# HbHandBoardMk2_V4.net
KiCad netlist of a schematic drawn in EAGLE
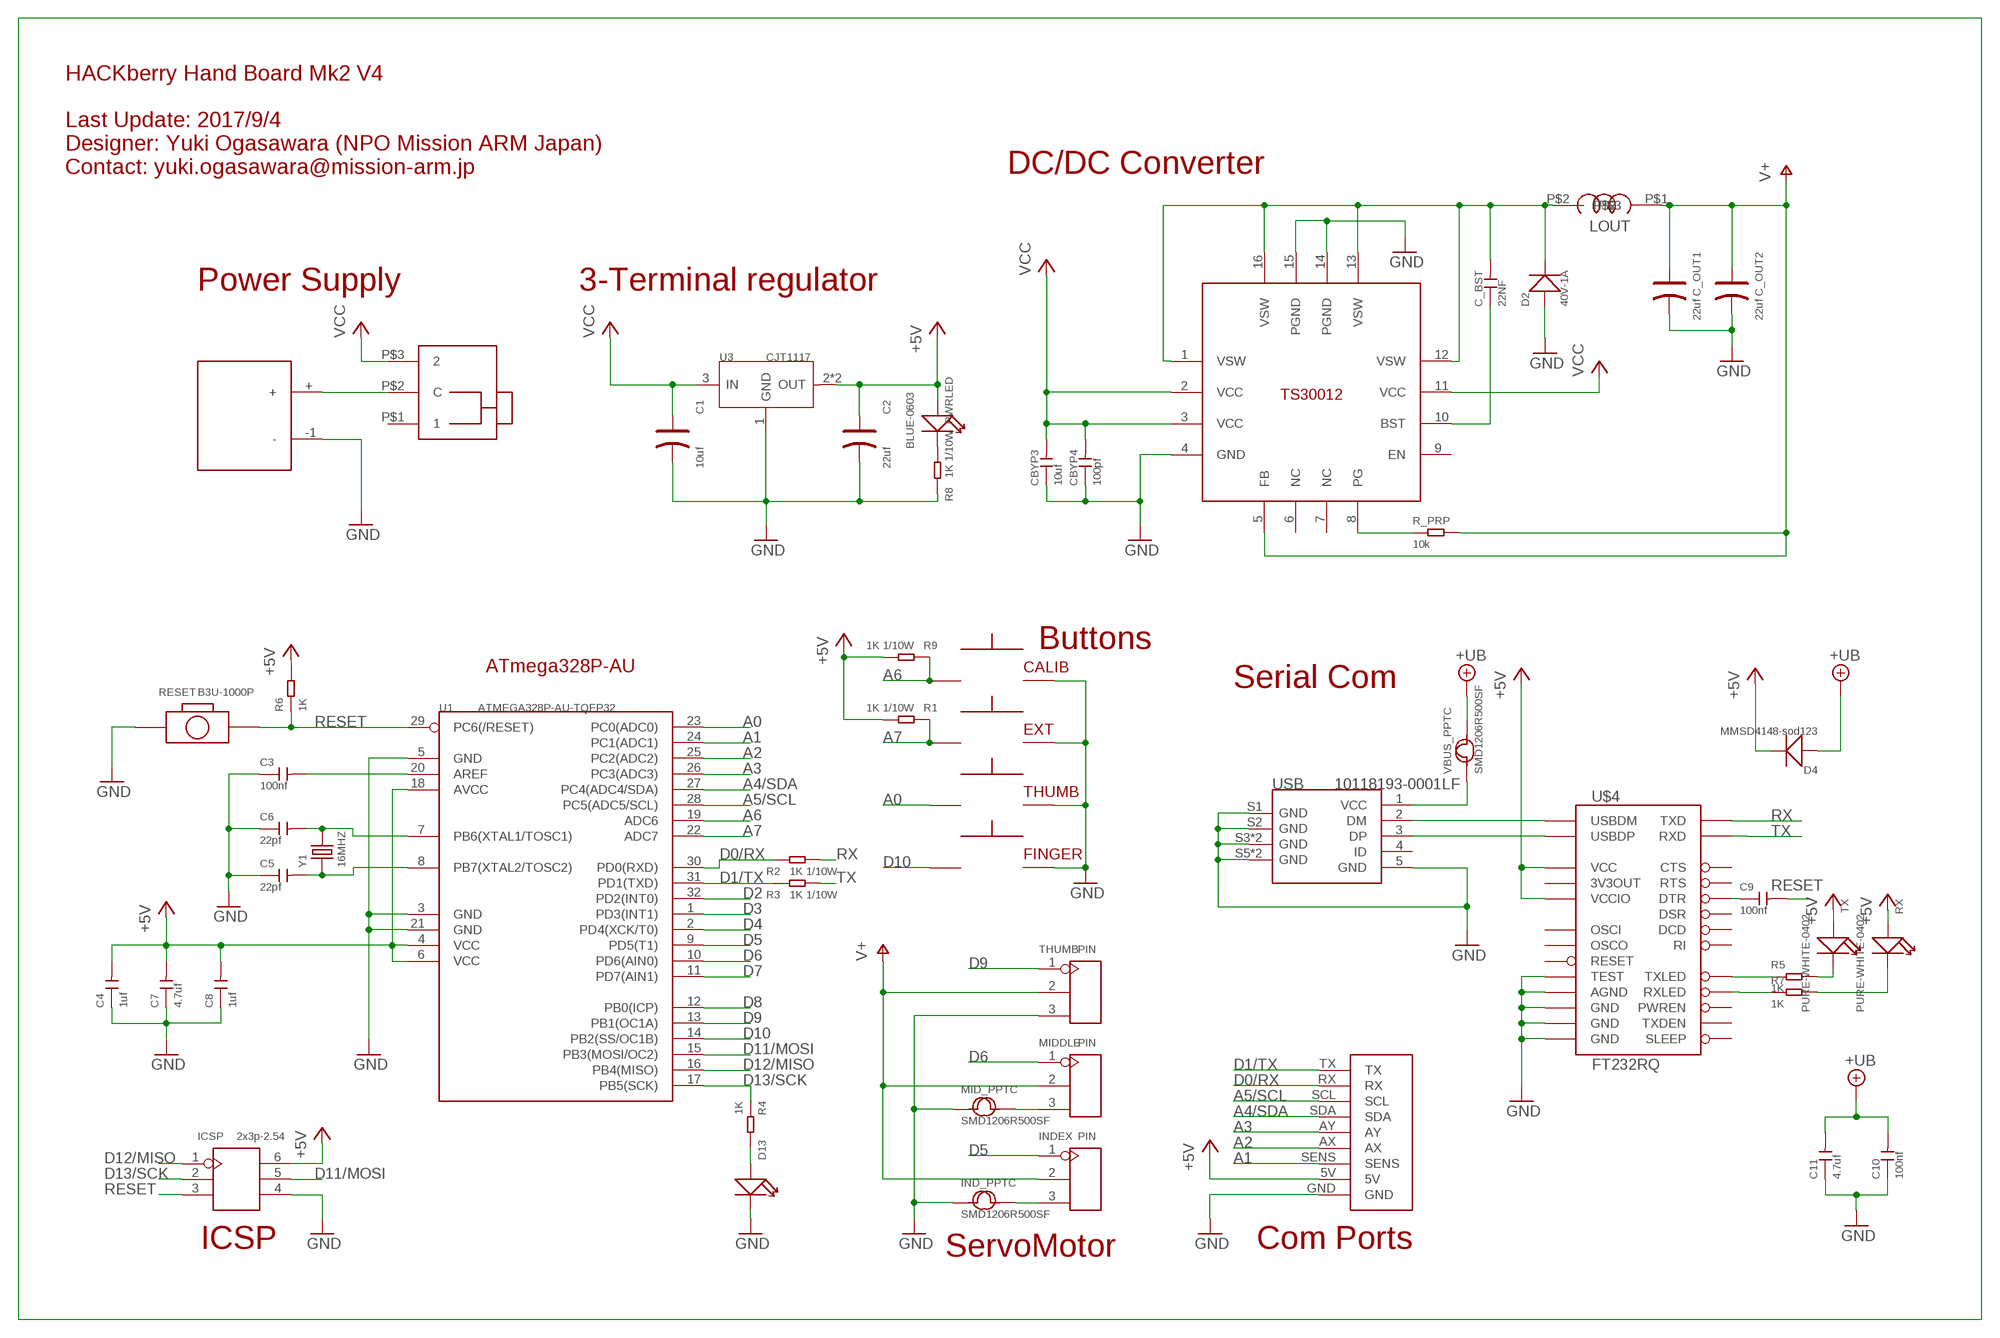
[diagram p0: schematic, sheet 1]

(export (version "E")
  (design (tool "Eeschema 10.0.6"))
  (components
    (comp (ref "C1")
      (value "10uf")
      (footprint "eagle-import:AVX-A")
      (fields (field (name "MPN") "TAJA106K010RNJ"))
      (libsource (lib "eagle-import") (part "TANTALUM-SMD-10UF-10V-10%(AVX-A)"))
    )
    (comp (ref "C2")
      (value "22uf")
      (footprint "eagle-import:AVX-A")
      (fields (field (name "MPN") "TAJA226*010#NJ"))
      (libsource (lib "eagle-import") (part "TANTALUM-SMD-22UF-10V(AVX-A)"))
    )
    (comp (ref "C3")
      (value "100nf")
      (footprint "eagle-import:C0402")
      (fields (field (name "MPN") "CC0402KRX7R8BB104"))
      (libsource (lib "eagle-import") (part "CERAMIC-100NF-25V-10%-X7R(0402)"))
    )
    (comp (ref "C4")
      (value "1uf")
      (footprint "eagle-import:C0402")
      (fields (field (name "MPN") "CC0402KRX5R6BB105"))
      (libsource (lib "eagle-import") (part "CERAMIC-1UF-10V-10%-X5R(0402)"))
    )
    (comp (ref "C5")
      (value "22pf")
      (footprint "eagle-import:C0402")
      (fields (field (name "MPN") "CC0402JRNPO9BN220"))
      (libsource (lib "eagle-import") (part "CERAMIC-22PF-50V-5%-NPO(0402)"))
    )
    (comp (ref "C6")
      (value "22pf")
      (footprint "eagle-import:C0402")
      (fields (field (name "MPN") "CC0402JRNPO9BN220"))
      (libsource (lib "eagle-import") (part "CERAMIC-22PF-50V-5%-NPO(0402)"))
    )
    (comp (ref "C7")
      (value "4.7uf")
      (footprint "eagle-import:C0603")
      (fields (field (name "MPN") "CC0603KRX5R6BB475"))
      (libsource (lib "eagle-import") (part "CERAMIC-4.7UF-10V-10%-X5R(0603)"))
    )
    (comp (ref "C8")
      (value "1uf")
      (footprint "eagle-import:C0402")
      (fields (field (name "MPN") "CC0402KRX5R6BB105"))
      (libsource (lib "eagle-import") (part "CERAMIC-1UF-10V-10%-X5R(0402)"))
    )
    (comp (ref "C9")
      (value "100nf")
      (footprint "eagle-import:C0402")
      (fields (field (name "MPN") "CC0402KRX7R8BB104"))
      (libsource (lib "eagle-import") (part "CERAMIC-100NF-25V-10%-X7R(0402)"))
    )
    (comp (ref "C10")
      (value "100nf")
      (footprint "eagle-import:C0402")
      (fields (field (name "MPN") "CC0402KRX7R8BB104"))
      (libsource (lib "eagle-import") (part "CERAMIC-100NF-25V-10%-X7R(0402)"))
    )
    (comp (ref "C11")
      (value "4.7uf")
      (footprint "eagle-import:C0603")
      (fields (field (name "MPN") "CC0603KRX5R6BB475"))
      (libsource (lib "eagle-import") (part "CERAMIC-4.7UF-10V-10%-X5R(0603)"))
    )
    (comp (ref "CALIB")
      (value "SKRGAQD010")
      (footprint "eagle-import:SKRGAQD010")
      (libsource (lib "eagle-import") (part "SKRGAQD010"))
    )
    (comp (ref "CBYP3")
      (value "10uf")
      (footprint "eagle-import:C0805")
      (fields (field (name "MPN") "CC0805KKX5R8BB106"))
      (libsource (lib "eagle-import") (part "CERAMIC-10UF-25V-10%-X5R(0805)"))
    )
    (comp (ref "CBYP4")
      (value "100pf")
      (footprint "eagle-import:C0402")
      (fields (field (name "MPN") "CC0402JRNPO9BN101"))
      (libsource (lib "eagle-import") (part "CERAMIC-100PF-50V-5%-NPO(0402)"))
    )
    (comp (ref "C_BST")
      (value "22NF")
      (footprint "eagle-import:C0402")
      (fields (field (name "MPN") "CC0402KRX7R9BB223"))
      (libsource (lib "eagle-import") (part "CERAMIC-22NF-50V-10%-X7R(0402)"))
    )
    (comp (ref "C_OUT1")
      (value "22uf")
      (footprint "eagle-import:AVX-B")
      (fields (field (name "MPN") "TAJB226K010RNJ"))
      (libsource (lib "eagle-import") (part "TANTALUM-SMD-22UF-10V-10%(AVX-B)"))
    )
    (comp (ref "C_OUT2")
      (value "22uf")
      (footprint "eagle-import:AVX-B")
      (fields (field (name "MPN") "TAJB226K010RNJ"))
      (libsource (lib "eagle-import") (part "TANTALUM-SMD-22UF-10V-10%(AVX-B)"))
    )
    (comp (ref "D2")
      (value "40V-1A")
      (footprint "eagle-import:DO-214AC")
      (fields (field (name "MPN") "1N5819"))
      (libsource (lib "eagle-import") (part "SMD-DIODE-SCHOTTKY-40V-1A(DO-214AC)"))
    )
    (comp (ref "D4")
      (value "MMSD4148-sod123")
      (footprint "eagle-import:SOD-123")
      (fields (field (name "MPN") "MMSD4148"))
      (libsource (lib "eagle-import") (part "SMD-DIODE-100V-200MA(SOD-123)"))
    )
    (comp (ref "D13")
      (value "SMD-LED-CLEAR-GREEN(0805)")
      (footprint "eagle-import:LED-0805")
      (fields (field (name "MPN") "17-215SYGC/S530-E2/TR8"))
      (libsource (lib "eagle-import") (part "SMD-LED-CLEAR-GREEN(0805)"))
    )
    (comp (ref "EXT")
      (value "SKRGAQD010")
      (footprint "eagle-import:SKRGAQD010")
      (libsource (lib "eagle-import") (part "SKRGAQD010"))
    )
    (comp (ref "FINGER")
      (value "SKRGAQD010")
      (footprint "eagle-import:SKRGAQD010")
      (libsource (lib "eagle-import") (part "SKRGAQD010"))
    )
    (comp (ref "ICSP")
      (value "2x3p-2.54")
      (footprint "eagle-import:H2X3-2.54")
      (fields (field (name "MPN") "P125-12A1BS116A1"))
      (libsource (lib "eagle-import") (part "DIP-BLACK-MALE-HEADER(2X3P-2.54）-2.54"))
    )
    (comp (ref "INDEX")
      (value "PIN")
      (footprint "eagle-import:H3-2.54")
      (fields (field (name "MPN") "F185-1103A0BSYA1"))
      (libsource (lib "eagle-import") (part "DIP-BLACK-FEMALE-HEADER-VERT(3P-2.54)"))
    )
    (comp (ref "IND_PPTC")
      (value "SMD1206R500SF")
      (footprint "eagle-import:F1206")
      (libsource (lib "eagle-import") (part "SMD-PPTC-500MA(1206)"))
    )
    (comp (ref "LOUT")
      (value "SPM3015T-4R7M-LR")
      (footprint "eagle-import:SPM3015T-4R7M-LR")
      (libsource (lib "eagle-import") (part "SPM3015T-4R7M-LR"))
    )
    (comp (ref "MIDDLE")
      (value "PIN")
      (footprint "eagle-import:H3-2.54")
      (fields (field (name "MPN") "F185-1103A0BSYA1"))
      (libsource (lib "eagle-import") (part "DIP-BLACK-FEMALE-HEADER-VERT(3P-2.54)"))
    )
    (comp (ref "MID_PPTC")
      (value "SMD1206R500SF")
      (footprint "eagle-import:F1206")
      (libsource (lib "eagle-import") (part "SMD-PPTC-500MA(1206)"))
    )
    (comp (ref "PWRLED")
      (value "BLUE-0603")
      (footprint "eagle-import:LED-0603")
      (fields (field (name "MPN") "19-217-BHC-ZL1M2RY-3T"))
      (libsource (lib "eagle-import") (part "SMD-LED-CLEAR-BLUE(0603)"))
    )
    (comp (ref "PWR_SW")
      (value "SS12SDP2")
      (footprint "eagle-import:SS12SDP2")
      (libsource (lib "eagle-import") (part "SS12SDP2"))
    )
    (comp (ref "R1")
      (value "1K 1/10W")
      (footprint "eagle-import:R0603")
      (fields (field (name "MPN") "RC0603JR-071KL"))
      (libsource (lib "eagle-import") (part "SMD-RES-1K-5%-1/10W(0603)"))
    )
    (comp (ref "R2")
      (value "1K 1/10W")
      (footprint "eagle-import:R0603")
      (fields (field (name "MPN") "RC0603JR-071KL"))
      (libsource (lib "eagle-import") (part "SMD-RES-1K-5%-1/10W(0603)"))
    )
    (comp (ref "R3")
      (value "1K 1/10W")
      (footprint "eagle-import:R0603")
      (fields (field (name "MPN") "RC0603JR-071KL"))
      (libsource (lib "eagle-import") (part "SMD-RES-1K-5%-1/10W(0603)"))
    )
    (comp (ref "R4")
      (value "1K")
      (footprint "eagle-import:R0805")
      (fields (field (name "MPN") "RC0805JR-071KL"))
      (libsource (lib "eagle-import") (part "SMD-RES-1K-5%-1/8W(0805)"))
    )
    (comp (ref "R5")
      (value "1K")
      (footprint "eagle-import:R0402")
      (fields (field (name "MPN") "RC0402JR-071KL"))
      (libsource (lib "eagle-import") (part "SMD-RES-1K-5%-1/16W(0402)"))
    )
    (comp (ref "R6")
      (value "1K")
      (footprint "eagle-import:R0402")
      (fields (field (name "MPN") "RC0402JR-071KL"))
      (libsource (lib "eagle-import") (part "SMD-RES-1K-5%-1/16W(0402)"))
    )
    (comp (ref "R7")
      (value "1K")
      (footprint "eagle-import:R0402")
      (fields (field (name "MPN") "RC0402JR-071KL"))
      (libsource (lib "eagle-import") (part "SMD-RES-1K-5%-1/16W(0402)"))
    )
    (comp (ref "R8")
      (value "1K 1/10W")
      (footprint "eagle-import:R0603")
      (fields (field (name "MPN") "RC0603JR-071KL"))
      (libsource (lib "eagle-import") (part "SMD-RES-1K-5%-1/10W(0603)"))
    )
    (comp (ref "R9")
      (value "1K 1/10W")
      (footprint "eagle-import:R0603")
      (fields (field (name "MPN") "RC0603JR-071KL"))
      (libsource (lib "eagle-import") (part "SMD-RES-1K-5%-1/10W(0603)"))
    )
    (comp (ref "RESET")
      (value "B3U-1000P")
      (footprint "eagle-import:SW2-SMD-3.0X2.5X1.2+0.4MM")
      (libsource (lib "eagle-import") (part "SMD-BUTTON-WITHOUT-BOSS-(2P-3X2.5MM)"))
    )
    (comp (ref "RX")
      (value "PURE-WHITE-0402")
      (footprint "eagle-import:LED-0402")
      (fields (field (name "MPN") "16-219A/T2D-AR2T1QY/3T"))
      (libsource (lib "eagle-import") (part "SMD-LED-YELLOW-DIFFUSED-PURE-WHITE(0402)"))
    )
    (comp (ref "R_PRP")
      (value "10k")
      (footprint "eagle-import:R0402")
      (libsource (lib "eagle-import") (part "RES-0402"))
    )
    (comp (ref "THUMB")
      (value "PIN")
      (footprint "eagle-import:H3-2.54")
      (fields (field (name "MPN") "F185-1103A0BSYA1"))
      (libsource (lib "eagle-import") (part "DIP-BLACK-FEMALE-HEADER-VERT(3P-2.54)"))
    )
    (comp (ref "THUMB_BUTTON")
      (value "SKRGAQD010")
      (footprint "eagle-import:SKRGAQD010")
      (libsource (lib "eagle-import") (part "SKRGAQD010"))
    )
    (comp (ref "TX")
      (value "PURE-WHITE-0402")
      (footprint "eagle-import:LED-0402")
      (fields (field (name "MPN") "16-219A/T2D-AR2T1QY/3T"))
      (libsource (lib "eagle-import") (part "SMD-LED-YELLOW-DIFFUSED-PURE-WHITE(0402)"))
    )
    (comp (ref "U$1")
      (value "9PADS")
      (footprint "eagle-import:9PADS")
      (libsource (lib "eagle-import") (part "9PADS"))
    )
    (comp (ref "U$3")
      (value "DCJACK")
      (footprint "eagle-import:DCJ3P-14.2X11.0X9.0MM")
      (libsource (lib "eagle-import") (part "DCJACK"))
    )
    (comp (ref "U$4")
      (value "FT232RQ")
      (footprint "eagle-import:QFN-32")
      (fields (field (name "MF") "FTDI"))
      (libsource (lib "eagle-import") (part "FT232RQ"))
    )
    (comp (ref "U$6")
      (value "TS30012")
      (footprint "eagle-import:VQFN16")
      (libsource (lib "eagle-import") (part "TS30012"))
    )
    (comp (ref "U1")
      (value "ATMEGA328P-AU-TQFP32")
      (footprint "eagle-import:TQFP32-0.8-7X7MM")
      (fields (field (name "MPN") "ATMEGA328P-AU"))
      (libsource (lib "eagle-import") (part "MCU-ATMEGA328P-AU(TQFP32)"))
    )
    (comp (ref "U3")
      (value "CJT1117")
      (footprint "eagle-import:SOT-223")
      (fields (field (name "MPN") "CJT1117-5.0"))
      (libsource (lib "eagle-import") (part "PMIC-CJT1117-5.0(SOT223)"))
    )
    (comp (ref "USB")
      (value "10118193-0001LF")
      (footprint "eagle-import:MICRO-USB5+6P-SMD-0.65-B")
      (libsource (lib "eagle-import") (part "MICRO-USB-SMD-B-(10118193-0001LF)"))
    )
    (comp (ref "VBUS_PPTC")
      (value "SMD1206R500SF")
      (footprint "eagle-import:F1206")
      (libsource (lib "eagle-import") (part "SMD-PPTC-500MA(1206)"))
    )
    (comp (ref "Y1")
      (value "16MHZ")
      (footprint "eagle-import:X2-SMD-5.0X3.2X1.3MM")
      (fields (field (name "MPN") "X053201602002"))
      (libsource (lib "eagle-import") (part "SMD-CRYSTAL-16MHZ-8PF-20PPM-40R(2P-5.0X3.2MM)"))
    )
  )
  (nets
    (net (code "1") (name "+5V") (class "Default")
      (node (ref "C2") (pin "+") (pinfunction "+_+") (pintype "passive"))
      (node (ref "C4") (pin "2") (pinfunction "2_2") (pintype "passive"))
      (node (ref "C7") (pin "2") (pinfunction "2_2") (pintype "passive"))
      (node (ref "C8") (pin "2") (pinfunction "2_2") (pintype "passive"))
      (node (ref "D4") (pin "-") (pinfunction "-_-") (pintype "passive"))
      (node (ref "ICSP") (pin "6") (pinfunction "6_6") (pintype "bidirectional"))
      (node (ref "PWRLED") (pin "+") (pinfunction "+_+") (pintype "passive"))
      (node (ref "R1") (pin "2") (pinfunction "2_2") (pintype "passive"))
      (node (ref "R6") (pin "2") (pinfunction "2_2") (pintype "passive"))
      (node (ref "R9") (pin "2") (pinfunction "2_2") (pintype "passive"))
      (node (ref "RX") (pin "+") (pinfunction "+_+") (pintype "passive"))
      (node (ref "TX") (pin "+") (pinfunction "+_+") (pintype "passive"))
      (node (ref "U$1") (pin "5V") (pinfunction "5V_5V") (pintype "bidirectional"))
      (node (ref "U$4") (pin "1") (pinfunction "VCCIO_1") (pintype "power_in"))
      (node (ref "U$4") (pin "19") (pinfunction "VCC_19") (pintype "power_in"))
      (node (ref "U1") (pin "18") (pinfunction "AVCC_18") (pintype "bidirectional"))
      (node (ref "U1") (pin "4") (pinfunction "VCC_4") (pintype "bidirectional"))
      (node (ref "U1") (pin "6") (pinfunction "VCC_6") (pintype "bidirectional"))
      (node (ref "U3") (pin "2") (pinfunction "OUT_2") (pintype "bidirectional"))
      (node (ref "U3") (pin "TER") (pinfunction "OUT_TER") (pintype "bidirectional"))
    )
    (net (code "2") (name "+UB") (class "Default")
      (node (ref "C10") (pin "2") (pinfunction "2_2") (pintype "passive"))
      (node (ref "C11") (pin "2") (pinfunction "2_2") (pintype "passive"))
      (node (ref "D4") (pin "+") (pinfunction "+_+") (pintype "passive"))
      (node (ref "VBUS_PPTC") (pin "2") (pinfunction "2_2") (pintype "bidirectional"))
    )
    (net (code "3") (name "/A0") (class "Default")
      (node (ref "THUMB_BUTTON") (pin "P$1") (pinfunction "1_P$1") (pintype "bidirectional"))
      (node (ref "U1") (pin "23") (pinfunction "PC0(ADC0)_23") (pintype "bidirectional"))
    )
    (net (code "4") (name "/A1") (class "Default")
      (node (ref "U$1") (pin "SENS") (pinfunction "SENS_SENS") (pintype "bidirectional"))
      (node (ref "U1") (pin "24") (pinfunction "PC1(ADC1)_24") (pintype "bidirectional"))
    )
    (net (code "5") (name "/A2") (class "Default")
      (node (ref "U$1") (pin "AX") (pinfunction "AX_AX") (pintype "bidirectional"))
      (node (ref "U1") (pin "25") (pinfunction "PC2(ADC2)_25") (pintype "bidirectional"))
    )
    (net (code "6") (name "/A3") (class "Default")
      (node (ref "U$1") (pin "AY") (pinfunction "AY_AY") (pintype "bidirectional"))
      (node (ref "U1") (pin "26") (pinfunction "PC3(ADC3)_26") (pintype "bidirectional"))
    )
    (net (code "7") (name "/A4{slash}SDA") (class "Default")
      (node (ref "U$1") (pin "SDA") (pinfunction "SDA_SDA") (pintype "bidirectional"))
      (node (ref "U1") (pin "27") (pinfunction "PC4(ADC4/SDA)_27") (pintype "bidirectional"))
    )
    (net (code "8") (name "/A5{slash}SCL") (class "Default")
      (node (ref "U$1") (pin "SCL") (pinfunction "SCL_SCL") (pintype "bidirectional"))
      (node (ref "U1") (pin "28") (pinfunction "PC5(ADC5/SCL)_28") (pintype "bidirectional"))
    )
    (net (code "9") (name "/A6") (class "Default")
      (node (ref "CALIB") (pin "P$1") (pinfunction "1_P$1") (pintype "bidirectional"))
      (node (ref "R9") (pin "1") (pinfunction "1_1") (pintype "passive"))
      (node (ref "U1") (pin "19") (pinfunction "ADC6_19") (pintype "bidirectional"))
    )
    (net (code "10") (name "/A7") (class "Default")
      (node (ref "EXT") (pin "P$1") (pinfunction "1_P$1") (pintype "bidirectional"))
      (node (ref "R1") (pin "1") (pinfunction "1_1") (pintype "passive"))
      (node (ref "U1") (pin "22") (pinfunction "ADC7_22") (pintype "bidirectional"))
    )
    (net (code "11") (name "/D0{slash}RX") (class "Default")
      (node (ref "R2") (pin "1") (pinfunction "1_1") (pintype "passive"))
      (node (ref "U$1") (pin "RX") (pinfunction "RX_RX") (pintype "bidirectional"))
      (node (ref "U1") (pin "30") (pinfunction "PD0(RXD)_30") (pintype "bidirectional"))
    )
    (net (code "12") (name "/D1{slash}TX") (class "Default")
      (node (ref "R3") (pin "1") (pinfunction "1_1") (pintype "passive"))
      (node (ref "U$1") (pin "TX") (pinfunction "TX_TX") (pintype "bidirectional"))
      (node (ref "U1") (pin "31") (pinfunction "PD1(TXD)_31") (pintype "bidirectional"))
    )
    (net (code "13") (name "/D2") (class "Default")
      (node (ref "U1") (pin "32") (pinfunction "PD2(INT0)_32") (pintype "bidirectional"))
    )
    (net (code "14") (name "/D3") (class "Default")
      (node (ref "U1") (pin "1") (pinfunction "PD3(INT1)_1") (pintype "bidirectional"))
    )
    (net (code "15") (name "/D4") (class "Default")
      (node (ref "U1") (pin "2") (pinfunction "PD4(XCK/T0)_2") (pintype "bidirectional"))
    )
    (net (code "16") (name "/D5") (class "Default")
      (node (ref "INDEX") (pin "1") (pinfunction "P$1_1") (pintype "bidirectional"))
      (node (ref "U1") (pin "9") (pinfunction "PD5(T1)_9") (pintype "bidirectional"))
    )
    (net (code "17") (name "/D6") (class "Default")
      (node (ref "MIDDLE") (pin "1") (pinfunction "P$1_1") (pintype "bidirectional"))
      (node (ref "U1") (pin "10") (pinfunction "PD6(AIN0)_10") (pintype "bidirectional"))
    )
    (net (code "18") (name "/D7") (class "Default")
      (node (ref "U1") (pin "11") (pinfunction "PD7(AIN1)_11") (pintype "bidirectional"))
    )
    (net (code "19") (name "/D8") (class "Default")
      (node (ref "U1") (pin "12") (pinfunction "PB0(ICP)_12") (pintype "bidirectional"))
    )
    (net (code "20") (name "/D9") (class "Default")
      (node (ref "THUMB") (pin "1") (pinfunction "P$1_1") (pintype "bidirectional"))
      (node (ref "U1") (pin "13") (pinfunction "PB1(OC1A)_13") (pintype "bidirectional"))
    )
    (net (code "21") (name "/D10") (class "Default")
      (node (ref "FINGER") (pin "P$1") (pinfunction "1_P$1") (pintype "bidirectional"))
      (node (ref "U1") (pin "14") (pinfunction "PB2(SS/OC1B)_14") (pintype "bidirectional"))
    )
    (net (code "22") (name "/D11{slash}MOSI") (class "Default")
      (node (ref "ICSP") (pin "5") (pinfunction "5_5") (pintype "bidirectional"))
      (node (ref "U1") (pin "15") (pinfunction "PB3(MOSI/OC2)_15") (pintype "bidirectional"))
    )
    (net (code "23") (name "/D12{slash}MISO") (class "Default")
      (node (ref "ICSP") (pin "1") (pinfunction "1_1") (pintype "bidirectional"))
      (node (ref "U1") (pin "16") (pinfunction "PB4(MISO)_16") (pintype "bidirectional"))
    )
    (net (code "24") (name "/D13{slash}SCK") (class "Default")
      (node (ref "ICSP") (pin "2") (pinfunction "2_2") (pintype "bidirectional"))
      (node (ref "R4") (pin "1") (pinfunction "1_1") (pintype "passive"))
      (node (ref "U1") (pin "17") (pinfunction "PB5(SCK)_17") (pintype "bidirectional"))
    )
    (net (code "25") (name "/RESET") (class "Default")
      (node (ref "C9") (pin "2") (pinfunction "2_2") (pintype "passive"))
      (node (ref "ICSP") (pin "3") (pinfunction "3_3") (pintype "bidirectional"))
      (node (ref "R6") (pin "1") (pinfunction "1_1") (pintype "passive"))
      (node (ref "RESET") (pin "2") (pinfunction "2_2") (pintype "bidirectional"))
      (node (ref "U1") (pin "29") (pinfunction "PC6(/RESET)_29") (pintype "bidirectional"))
    )
    (net (code "26") (name "/RX") (class "Default")
      (node (ref "R2") (pin "2") (pinfunction "2_2") (pintype "passive"))
      (node (ref "U$4") (pin "30") (pinfunction "TXD_30") (pintype "output"))
    )
    (net (code "27") (name "/TX") (class "Default")
      (node (ref "R3") (pin "2") (pinfunction "2_2") (pintype "passive"))
      (node (ref "U$4") (pin "2") (pinfunction "RXD_2") (pintype "input"))
    )
    (net (code "28") (name "GND") (class "Default")
      (node (ref "C1") (pin "-") (pinfunction "-_-") (pintype "passive"))
      (node (ref "C10") (pin "1") (pinfunction "1_1") (pintype "passive"))
      (node (ref "C11") (pin "1") (pinfunction "1_1") (pintype "passive"))
      (node (ref "C2") (pin "-") (pinfunction "-_-") (pintype "passive"))
      (node (ref "C3") (pin "1") (pinfunction "1_1") (pintype "passive"))
      (node (ref "C4") (pin "1") (pinfunction "1_1") (pintype "passive"))
      (node (ref "C5") (pin "1") (pinfunction "1_1") (pintype "passive"))
      (node (ref "C6") (pin "1") (pinfunction "1_1") (pintype "passive"))
      (node (ref "C7") (pin "1") (pinfunction "1_1") (pintype "passive"))
      (node (ref "C8") (pin "1") (pinfunction "1_1") (pintype "passive"))
      (node (ref "CALIB") (pin "P$2") (pinfunction "2_P$2") (pintype "bidirectional"))
      (node (ref "CBYP3") (pin "1") (pinfunction "1_1") (pintype "passive"))
      (node (ref "CBYP4") (pin "1") (pinfunction "1_1") (pintype "passive"))
      (node (ref "C_OUT1") (pin "-") (pinfunction "-_-") (pintype "passive"))
      (node (ref "C_OUT2") (pin "-") (pinfunction "-_-") (pintype "passive"))
      (node (ref "D13") (pin "-") (pinfunction "-_-") (pintype "passive"))
      (node (ref "D2") (pin "1") (pinfunction "+_1") (pintype "passive"))
      (node (ref "EXT") (pin "P$2") (pinfunction "2_P$2") (pintype "bidirectional"))
      (node (ref "FINGER") (pin "P$2") (pinfunction "2_P$2") (pintype "bidirectional"))
      (node (ref "ICSP") (pin "4") (pinfunction "4_4") (pintype "bidirectional"))
      (node (ref "IND_PPTC") (pin "1") (pinfunction "1_1") (pintype "bidirectional"))
      (node (ref "MID_PPTC") (pin "1") (pinfunction "1_1") (pintype "bidirectional"))
      (node (ref "R8") (pin "1") (pinfunction "1_1") (pintype "passive"))
      (node (ref "RESET") (pin "1") (pinfunction "1_1") (pintype "bidirectional"))
      (node (ref "THUMB") (pin "3") (pinfunction "P$3_3") (pintype "bidirectional"))
      (node (ref "THUMB_BUTTON") (pin "P$2") (pinfunction "2_P$2") (pintype "bidirectional"))
      (node (ref "U$1") (pin "GND") (pinfunction "GND_GND") (pintype "bidirectional"))
      (node (ref "U$3") (pin "-1") (pinfunction "-_-1") (pintype "bidirectional"))
      (node (ref "U$4") (pin "17") (pinfunction "GND_17") (pintype "power_in"))
      (node (ref "U$4") (pin "20") (pinfunction "GND_20") (pintype "power_in"))
      (node (ref "U$4") (pin "24") (pinfunction "AGND_24") (pintype "power_in"))
      (node (ref "U$4") (pin "26") (pinfunction "TEST_26") (pintype "input"))
      (node (ref "U$4") (pin "4") (pinfunction "GND_4") (pintype "power_in"))
      (node (ref "U$6") (pin "14") (pinfunction "PGND_14") (pintype "bidirectional"))
      (node (ref "U$6") (pin "15") (pinfunction "PGND_15") (pintype "bidirectional"))
      (node (ref "U$6") (pin "4") (pinfunction "GND_4") (pintype "bidirectional"))
      (node (ref "U1") (pin "21") (pinfunction "GND_21") (pintype "bidirectional"))
      (node (ref "U1") (pin "3") (pinfunction "GND_3") (pintype "bidirectional"))
      (node (ref "U1") (pin "5") (pinfunction "GND_5") (pintype "bidirectional"))
      (node (ref "U3") (pin "1") (pinfunction "GND_1") (pintype "bidirectional"))
      (node (ref "USB") (pin "5") (pinfunction "GND_5") (pintype "bidirectional"))
      (node (ref "USB") (pin "S1") (pinfunction "GND_S1") (pintype "bidirectional"))
      (node (ref "USB") (pin "S2") (pinfunction "GND_S2") (pintype "bidirectional"))
      (node (ref "USB") (pin "S3") (pinfunction "GND_S3") (pintype "bidirectional"))
      (node (ref "USB") (pin "S4") (pinfunction "GND_S4") (pintype "bidirectional"))
      (node (ref "USB") (pin "S5") (pinfunction "GND_S5") (pintype "bidirectional"))
      (node (ref "USB") (pin "S6") (pinfunction "GND_S6") (pintype "bidirectional"))
    )
    (net (code "29") (name "Net-(D2--)") (class "Default")
      (node (ref "C_BST") (pin "2") (pinfunction "2_2") (pintype "passive"))
      (node (ref "D2") (pin "2") (pinfunction "-_2") (pintype "passive"))
      (node (ref "LOUT") (pin "P$2") (pinfunction "P$3_P$2") (pintype "bidirectional"))
      (node (ref "U$6") (pin "1") (pinfunction "VSW_1") (pintype "bidirectional"))
      (node (ref "U$6") (pin "12") (pinfunction "VSW_12") (pintype "bidirectional"))
      (node (ref "U$6") (pin "13") (pinfunction "VSW_13") (pintype "bidirectional"))
      (node (ref "U$6") (pin "16") (pinfunction "VSW_16") (pintype "bidirectional"))
    )
    (net (code "30") (name "Net-(D13-Pad+)") (class "Default")
      (node (ref "D13") (pin "+") (pinfunction "+_+") (pintype "passive"))
      (node (ref "R4") (pin "2") (pinfunction "2_2") (pintype "passive"))
    )
    (net (code "31") (name "Net-(INDEX-P$3)") (class "Default")
      (node (ref "INDEX") (pin "3") (pinfunction "P$3_3") (pintype "bidirectional"))
      (node (ref "IND_PPTC") (pin "2") (pinfunction "2_2") (pintype "bidirectional"))
    )
    (net (code "32") (name "Net-(MIDDLE-P$3)") (class "Default")
      (node (ref "MIDDLE") (pin "3") (pinfunction "P$3_3") (pintype "bidirectional"))
      (node (ref "MID_PPTC") (pin "2") (pinfunction "2_2") (pintype "bidirectional"))
    )
    (net (code "33") (name "Net-(PWRLED-Pad-)") (class "Default")
      (node (ref "PWRLED") (pin "-") (pinfunction "-_-") (pintype "passive"))
      (node (ref "R8") (pin "2") (pinfunction "2_2") (pintype "passive"))
    )
    (net (code "34") (name "Net-(PWR_SW-C)") (class "Default")
      (node (ref "PWR_SW") (pin "P$2") (pinfunction "C_P$2") (pintype "bidirectional"))
      (node (ref "U$3") (pin "+") (pinfunction "+_+") (pintype "bidirectional"))
    )
    (net (code "35") (name "Net-(R5-Pad2)") (class "Default")
      (node (ref "R5") (pin "2") (pinfunction "2_2") (pintype "passive"))
      (node (ref "TX") (pin "-") (pinfunction "-_-") (pintype "passive"))
    )
    (net (code "36") (name "Net-(R7-Pad2)") (class "Default")
      (node (ref "R7") (pin "2") (pinfunction "2_2") (pintype "passive"))
      (node (ref "RX") (pin "-") (pinfunction "-_-") (pintype "passive"))
    )
    (net (code "37") (name "Net-(U$4-DTR)") (class "Default")
      (node (ref "C9") (pin "1") (pinfunction "1_1") (pintype "passive"))
      (node (ref "U$4") (pin "31") (pinfunction "DTR_31") (pintype "output"))
    )
    (net (code "38") (name "Net-(U$4-RXLED)") (class "Default")
      (node (ref "R7") (pin "1") (pinfunction "1_1") (pintype "passive"))
      (node (ref "U$4") (pin "21") (pinfunction "RXLED_21") (pintype "input"))
    )
    (net (code "39") (name "Net-(U$4-TXLED)") (class "Default")
      (node (ref "R5") (pin "1") (pinfunction "1_1") (pintype "passive"))
      (node (ref "U$4") (pin "22") (pinfunction "TXLED_22") (pintype "input"))
    )
    (net (code "40") (name "Net-(U$4-USBDM)") (class "Default")
      (node (ref "U$4") (pin "15") (pinfunction "USBDM_15") (pintype "bidirectional"))
      (node (ref "USB") (pin "2") (pinfunction "DM_2") (pintype "bidirectional"))
    )
    (net (code "41") (name "Net-(U$4-USBDP)") (class "Default")
      (node (ref "U$4") (pin "14") (pinfunction "USBDP_14") (pintype "bidirectional"))
      (node (ref "USB") (pin "3") (pinfunction "DP_3") (pintype "bidirectional"))
    )
    (net (code "42") (name "Net-(U$6-BST)") (class "Default")
      (node (ref "C_BST") (pin "1") (pinfunction "1_1") (pintype "passive"))
      (node (ref "U$6") (pin "10") (pinfunction "BST_10") (pintype "bidirectional"))
    )
    (net (code "43") (name "Net-(U$6-PG)") (class "Default")
      (node (ref "R_PRP") (pin "1") (pinfunction "1_1") (pintype "passive"))
      (node (ref "U$6") (pin "8") (pinfunction "PG_8") (pintype "bidirectional"))
    )
    (net (code "44") (name "Net-(U1-AREF)") (class "Default")
      (node (ref "C3") (pin "2") (pinfunction "2_2") (pintype "passive"))
      (node (ref "U1") (pin "20") (pinfunction "AREF_20") (pintype "bidirectional"))
    )
    (net (code "45") (name "Net-(U1-PB6(XTAL1{slash}TOSC1))") (class "Default")
      (node (ref "C6") (pin "2") (pinfunction "2_2") (pintype "passive"))
      (node (ref "U1") (pin "7") (pinfunction "PB6(XTAL1/TOSC1)_7") (pintype "bidirectional"))
      (node (ref "Y1") (pin "2") (pinfunction "2_2") (pintype "passive"))
    )
    (net (code "46") (name "Net-(U1-PB7(XTAL2{slash}TOSC2))") (class "Default")
      (node (ref "C5") (pin "2") (pinfunction "2_2") (pintype "passive"))
      (node (ref "U1") (pin "8") (pinfunction "PB7(XTAL2/TOSC2)_8") (pintype "bidirectional"))
      (node (ref "Y1") (pin "1") (pinfunction "1_1") (pintype "passive"))
    )
    (net (code "47") (name "Net-(USB-VCC)") (class "Default")
      (node (ref "USB") (pin "1") (pinfunction "VCC_1") (pintype "bidirectional"))
      (node (ref "VBUS_PPTC") (pin "1") (pinfunction "1_1") (pintype "bidirectional"))
    )
    (net (code "48") (name "V+") (class "Default")
      (node (ref "C_OUT1") (pin "+") (pinfunction "+_+") (pintype "passive"))
      (node (ref "C_OUT2") (pin "+") (pinfunction "+_+") (pintype "passive"))
      (node (ref "INDEX") (pin "2") (pinfunction "P$2_2") (pintype "bidirectional"))
      (node (ref "LOUT") (pin "P$1") (pinfunction "P$2_P$1") (pintype "bidirectional"))
      (node (ref "MIDDLE") (pin "2") (pinfunction "P$2_2") (pintype "bidirectional"))
      (node (ref "R_PRP") (pin "2") (pinfunction "2_2") (pintype "passive"))
      (node (ref "THUMB") (pin "2") (pinfunction "P$2_2") (pintype "bidirectional"))
      (node (ref "U$6") (pin "5") (pinfunction "FB_5") (pintype "bidirectional"))
    )
    (net (code "49") (name "VCC") (class "Default")
      (node (ref "C1") (pin "+") (pinfunction "+_+") (pintype "passive"))
      (node (ref "CBYP3") (pin "2") (pinfunction "2_2") (pintype "passive"))
      (node (ref "CBYP4") (pin "2") (pinfunction "2_2") (pintype "passive"))
      (node (ref "PWR_SW") (pin "P$3") (pinfunction "2_P$3") (pintype "bidirectional"))
      (node (ref "U$6") (pin "11") (pinfunction "VCC_11") (pintype "bidirectional"))
      (node (ref "U$6") (pin "2") (pinfunction "VCC_2") (pintype "bidirectional"))
      (node (ref "U$6") (pin "3") (pinfunction "VCC_3") (pintype "bidirectional"))
      (node (ref "U3") (pin "3") (pinfunction "IN_3") (pintype "bidirectional"))
    )
    (net (code "50") (name "unconnected-(PWR_SW-1-PadP$1)") (class "Default")
      (node (ref "PWR_SW") (pin "P$1") (pinfunction "1_P$1") (pintype "bidirectional"))
    )
    (net (code "51") (name "unconnected-(U$4-3V3OUT-Pad16)") (class "Default")
      (node (ref "U$4") (pin "16") (pinfunction "3V3OUT_16") (pintype "output"))
    )
    (net (code "52") (name "unconnected-(U$4-CTS-Pad8)") (class "Default")
      (node (ref "U$4") (pin "8") (pinfunction "CTS_8") (pintype "input"))
    )
    (net (code "53") (name "unconnected-(U$4-DCD-Pad7)") (class "Default")
      (node (ref "U$4") (pin "7") (pinfunction "DCD_7") (pintype "input"))
    )
    (net (code "54") (name "unconnected-(U$4-DSR-Pad6)") (class "Default")
      (node (ref "U$4") (pin "6") (pinfunction "DSR_6") (pintype "input"))
    )
    (net (code "55") (name "unconnected-(U$4-OSCI-Pad27)") (class "Default")
      (node (ref "U$4") (pin "27") (pinfunction "OSCI_27") (pintype "input"))
    )
    (net (code "56") (name "unconnected-(U$4-OSCO-Pad28)") (class "Default")
      (node (ref "U$4") (pin "28") (pinfunction "OSCO_28") (pintype "output"))
    )
    (net (code "57") (name "unconnected-(U$4-PWREN-Pad11)") (class "Default")
      (node (ref "U$4") (pin "11") (pinfunction "PWREN_11") (pintype "input"))
    )
    (net (code "58") (name "unconnected-(U$4-RESET-Pad18)") (class "Default")
      (node (ref "U$4") (pin "18") (pinfunction "RESET_18") (pintype "input"))
    )
    (net (code "59") (name "unconnected-(U$4-RI-Pad3)") (class "Default")
      (node (ref "U$4") (pin "3") (pinfunction "RI_3") (pintype "input"))
    )
    (net (code "60") (name "unconnected-(U$4-RTS-Pad32)") (class "Default")
      (node (ref "U$4") (pin "32") (pinfunction "RTS_32") (pintype "output"))
    )
    (net (code "61") (name "unconnected-(U$4-SLEEP-Pad9)") (class "Default")
      (node (ref "U$4") (pin "9") (pinfunction "SLEEP_9") (pintype "input"))
    )
    (net (code "62") (name "unconnected-(U$4-TXDEN-Pad10)") (class "Default")
      (node (ref "U$4") (pin "10") (pinfunction "TXDEN_10") (pintype "input"))
    )
    (net (code "63") (name "unconnected-(U$6-EN-Pad9)") (class "Default")
      (node (ref "U$6") (pin "9") (pinfunction "EN_9") (pintype "bidirectional"))
    )
    (net (code "64") (name "unconnected-(U$6-NC-Pad6)") (class "Default")
      (node (ref "U$6") (pin "6") (pinfunction "NC_6") (pintype "no_connect"))
    )
    (net (code "65") (name "unconnected-(U$6-NC-Pad7)") (class "Default")
      (node (ref "U$6") (pin "7") (pinfunction "NC_7") (pintype "no_connect"))
    )
    (net (code "66") (name "unconnected-(USB-ID-Pad4)") (class "Default")
      (node (ref "USB") (pin "4") (pinfunction "ID_4") (pintype "bidirectional"))
    )
  )
)
